# MP_Relay_Control.net
KiCad netlist of a schematic drawn in Altium Designer
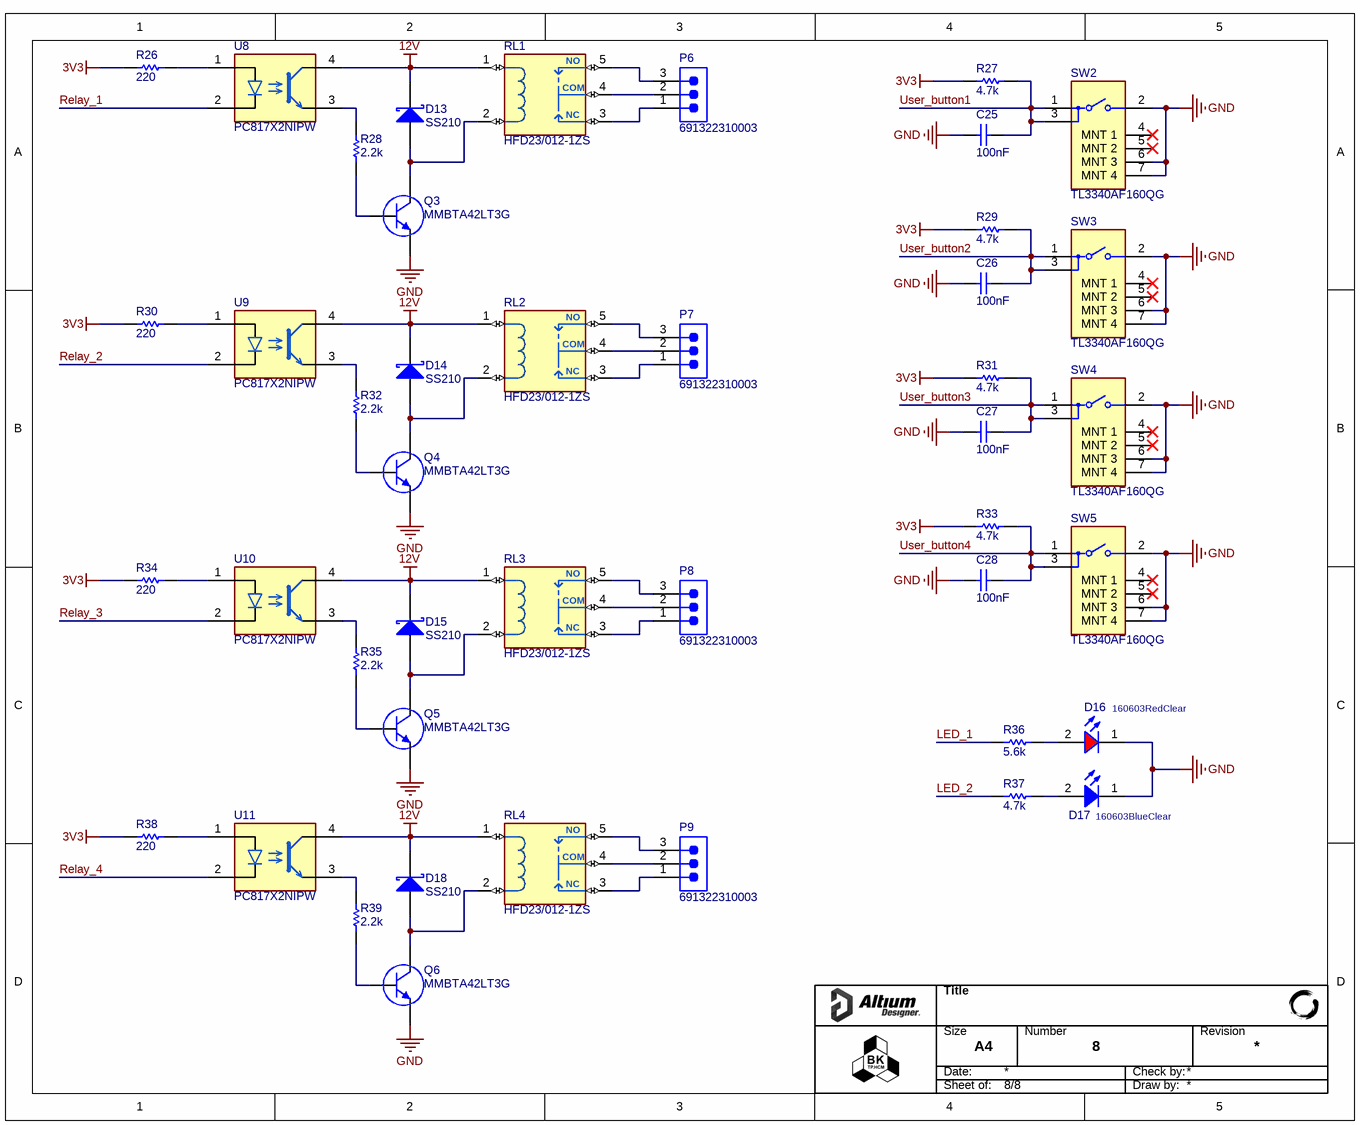
[diagram p0: [MP] Relay Control.SchDoc]

(export (version "E")
  (design (tool "Eeschema 10.0.6"))
  (components
    (comp (ref "C25")
      (value "100nF")
      (footprint "CAP_0603")
      (description "CAP, size 0603, 100 nF, 50 VDC, 10%")
      (fields
        (field (name "TOLERANCE") "10%")
        (field (name "LCSC PART #") "C14663")
        (field (name "SOURCE") "Capacitor_0603_10_percent.SchLib")
      )
      (libsource (lib "University of Technology") (part "010603475106.3"))
    )
    (comp (ref "C26")
      (value "100nF")
      (footprint "CAP_0603")
      (description "CAP, size 0603, 100 nF, 50 VDC, 10%")
      (fields
        (field (name "TOLERANCE") "10%")
        (field (name "LCSC PART #") "C14663")
        (field (name "SOURCE") "Capacitor_0603_10_percent.SchLib")
      )
      (libsource (lib "University of Technology") (part "010603475106.3"))
    )
    (comp (ref "C27")
      (value "100nF")
      (footprint "CAP_0603")
      (description "CAP, size 0603, 100 nF, 50 VDC, 10%")
      (fields
        (field (name "TOLERANCE") "10%")
        (field (name "LCSC PART #") "C14663")
        (field (name "SOURCE") "Capacitor_0603_10_percent.SchLib")
      )
      (libsource (lib "University of Technology") (part "010603475106.3"))
    )
    (comp (ref "C28")
      (value "100nF")
      (footprint "CAP_0603")
      (description "CAP, size 0603, 100 nF, 50 VDC, 10%")
      (fields
        (field (name "TOLERANCE") "10%")
        (field (name "LCSC PART #") "C14663")
        (field (name "SOURCE") "Capacitor_0603_10_percent.SchLib")
      )
      (libsource (lib "University of Technology") (part "010603475106.3"))
    )
    (comp (ref "D13")
      (value "SS210")
      (footprint "SS210-Footprint-SMA")
      (description "Rectifier Diode, Schottky, 1 Phase, 1 Element, 1.5A, 100V V(RRM), Silicon, DO-214AA")
      (libsource (lib "University of Technology") (part "SS210"))
    )
    (comp (ref "D14")
      (value "SS210")
      (footprint "SS210-Footprint-SMA")
      (description "Rectifier Diode, Schottky, 1 Phase, 1 Element, 1.5A, 100V V(RRM), Silicon, DO-214AA")
      (libsource (lib "University of Technology") (part "SS210"))
    )
    (comp (ref "D15")
      (value "SS210")
      (footprint "SS210-Footprint-SMA")
      (description "Rectifier Diode, Schottky, 1 Phase, 1 Element, 1.5A, 100V V(RRM), Silicon, DO-214AA")
      (libsource (lib "University of Technology") (part "SS210"))
    )
    (comp (ref "D16")
      (value "160603RedClear")
      (footprint "WL-SMCW_0603_H=0.7mm")
      (description "WL-SMCW SMT Mono-color Chip LED Waterclear, size 0603, Red, 2V, 140deg")
      (libsource (lib "University of Technology") (part "160603RedClear"))
    )
    (comp (ref "D17")
      (value "160603BlueClear")
      (footprint "WL-SMCW_0603_H=0.7mm")
      (description "WL-SMCW SMT Mono-color Chip LED Waterclear, size 0603, Blue, 3.2V, 140deg")
      (libsource (lib "University of Technology") (part "160603BlueClear"))
    )
    (comp (ref "D18")
      (value "SS210")
      (footprint "SS210-Footprint-SMA")
      (description "Rectifier Diode, Schottky, 1 Phase, 1 Element, 1.5A, 100V V(RRM), Silicon, DO-214AA")
      (libsource (lib "University of Technology") (part "SS210"))
    )
    (comp (ref "P6")
      (value "691322310003")
      (footprint "691322310003")
      (description "WR-TBL Series 322 Horizontal PCB Header, THT, pitch 3.81mm, 3p")
      (fields
        (field (name "MANUFACTURER") "Wurth Elektronik")
        (field (name "SOURCE") "Terminal_Blocks_Pluggable_3.81mm.SchLib")
      )
      (libsource (lib "University of Technology") (part "691322310003"))
    )
    (comp (ref "P7")
      (value "691322310003")
      (footprint "691322310003")
      (description "WR-TBL Series 322 Horizontal PCB Header, THT, pitch 3.81mm, 3p")
      (fields
        (field (name "MANUFACTURER") "Wurth Elektronik")
        (field (name "SOURCE") "Terminal_Blocks_Pluggable_3.81mm.SchLib")
      )
      (libsource (lib "University of Technology") (part "691322310003"))
    )
    (comp (ref "P8")
      (value "691322310003")
      (footprint "691322310003")
      (description "WR-TBL Series 322 Horizontal PCB Header, THT, pitch 3.81mm, 3p")
      (fields
        (field (name "MANUFACTURER") "Wurth Elektronik")
        (field (name "SOURCE") "Terminal_Blocks_Pluggable_3.81mm.SchLib")
      )
      (libsource (lib "University of Technology") (part "691322310003"))
    )
    (comp (ref "P9")
      (value "691322310003")
      (footprint "691322310003")
      (description "WR-TBL Series 322 Horizontal PCB Header, THT, pitch 3.81mm, 3p")
      (fields
        (field (name "MANUFACTURER") "Wurth Elektronik")
        (field (name "SOURCE") "Terminal_Blocks_Pluggable_3.81mm.SchLib")
      )
      (libsource (lib "University of Technology") (part "691322310003"))
    )
    (comp (ref "Q3")
      (value "MMBTA42LT3G")
      (footprint "ONSC-SOT-23-3-318-08_V")
      (description "Small Signal Bipolar Transistor, 0.5A I(C), 300V V(BR)CEO, 1-Element, NPN, Silicon, TO-236AB")
      (libsource (lib "University of Technology") (part "TRANS-NPN-3"))
    )
    (comp (ref "Q4")
      (value "MMBTA42LT3G")
      (footprint "ONSC-SOT-23-3-318-08_V")
      (description "Small Signal Bipolar Transistor, 0.5A I(C), 300V V(BR)CEO, 1-Element, NPN, Silicon, TO-236AB")
      (libsource (lib "University of Technology") (part "TRANS-NPN-3"))
    )
    (comp (ref "Q5")
      (value "MMBTA42LT3G")
      (footprint "ONSC-SOT-23-3-318-08_V")
      (description "Small Signal Bipolar Transistor, 0.5A I(C), 300V V(BR)CEO, 1-Element, NPN, Silicon, TO-236AB")
      (libsource (lib "University of Technology") (part "TRANS-NPN-3"))
    )
    (comp (ref "Q6")
      (value "MMBTA42LT3G")
      (footprint "ONSC-SOT-23-3-318-08_V")
      (description "Small Signal Bipolar Transistor, 0.5A I(C), 300V V(BR)CEO, 1-Element, NPN, Silicon, TO-236AB")
      (libsource (lib "University of Technology") (part "TRANS-NPN-3"))
    )
    (comp (ref "R26")
      (value "220")
      (footprint "RES_0603")
      (description "RES, size 0603, 220 Ohm, 1/10 W, 1%")
      (fields (field (name "TOLERANCE") "1%") (field (name "MANUFACTURER") "YAGEO"))
      (libsource (lib "University of Technology") (part "00060371541"))
    )
    (comp (ref "R27")
      (value "4.7k")
      (footprint "RES_0603")
      (description "RES, size 0603, 4.7 kOhm, 1/10 W, 1%")
      (fields (field (name "LCSC PART #") "C99782") (field (name "MANUFACTURER") "YAGEO"))
      (libsource (lib "University of Technology") (part "00060371541"))
    )
    (comp (ref "R28")
      (value "2.2k")
      (footprint "RES_0603")
      (description "RES, size 0603, 2.2  KOhm, 1/10 W, 1%")
      (fields (field (name "TOLERANCE") "1%") (field (name "MANUFACTURER PART NUMBER") "OEM"))
      (libsource (lib "University of Technology") (part "00060371541"))
    )
    (comp (ref "R29")
      (value "4.7k")
      (footprint "RES_0603")
      (description "RES, size 0603, 4.7 kOhm, 1/10 W, 1%")
      (fields (field (name "LCSC PART #") "C99782") (field (name "MANUFACTURER") "YAGEO"))
      (libsource (lib "University of Technology") (part "00060371541"))
    )
    (comp (ref "R30")
      (value "220")
      (footprint "RES_0603")
      (description "RES, size 0603, 220 Ohm, 1/10 W, 1%")
      (fields (field (name "TOLERANCE") "1%") (field (name "MANUFACTURER") "YAGEO"))
      (libsource (lib "University of Technology") (part "00060371541"))
    )
    (comp (ref "R31")
      (value "4.7k")
      (footprint "RES_0603")
      (description "RES, size 0603, 4.7 kOhm, 1/10 W, 1%")
      (fields (field (name "LCSC PART #") "C99782") (field (name "MANUFACTURER") "YAGEO"))
      (libsource (lib "University of Technology") (part "00060371541"))
    )
    (comp (ref "R32")
      (value "2.2k")
      (footprint "RES_0603")
      (description "RES, size 0603, 2.2  KOhm, 1/10 W, 1%")
      (fields (field (name "TOLERANCE") "1%") (field (name "MANUFACTURER PART NUMBER") "OEM"))
      (libsource (lib "University of Technology") (part "00060371541"))
    )
    (comp (ref "R33")
      (value "4.7k")
      (footprint "RES_0603")
      (description "RES, size 0603, 4.7 kOhm, 1/10 W, 1%")
      (fields (field (name "LCSC PART #") "C99782") (field (name "MANUFACTURER") "YAGEO"))
      (libsource (lib "University of Technology") (part "00060371541"))
    )
    (comp (ref "R34")
      (value "220")
      (footprint "RES_0603")
      (description "RES, size 0603, 220 Ohm, 1/10 W, 1%")
      (fields (field (name "TOLERANCE") "1%") (field (name "MANUFACTURER") "YAGEO"))
      (libsource (lib "University of Technology") (part "00060371541"))
    )
    (comp (ref "R35")
      (value "2.2k")
      (footprint "RES_0603")
      (description "RES, size 0603, 2.2  KOhm, 1/10 W, 1%")
      (fields (field (name "TOLERANCE") "1%") (field (name "MANUFACTURER PART NUMBER") "OEM"))
      (libsource (lib "University of Technology") (part "00060371541"))
    )
    (comp (ref "R36")
      (value "5.6k")
      (footprint "RES_0603")
      (description "RES, size 0603, 5.6 KOhm, 1/10 W, 1%")
      (fields (field (name "MANUFACTURER PART NUMBER") "OEM") (field (name "TOLERANCE") "1%"))
      (libsource (lib "University of Technology") (part "00060371541"))
    )
    (comp (ref "R37")
      (value "4.7k")
      (footprint "RES_0603")
      (description "RES, size 0603, 4.7 kOhm, 1/10 W, 1%")
      (fields (field (name "LCSC PART #") "C99782") (field (name "MANUFACTURER") "YAGEO"))
      (libsource (lib "University of Technology") (part "00060371541"))
    )
    (comp (ref "R38")
      (value "220")
      (footprint "RES_0603")
      (description "RES, size 0603, 220 Ohm, 1/10 W, 1%")
      (fields (field (name "TOLERANCE") "1%") (field (name "MANUFACTURER") "YAGEO"))
      (libsource (lib "University of Technology") (part "00060371541"))
    )
    (comp (ref "R39")
      (value "2.2k")
      (footprint "RES_0603")
      (description "RES, size 0603, 2.2  KOhm, 1/10 W, 1%")
      (fields (field (name "TOLERANCE") "1%") (field (name "MANUFACTURER PART NUMBER") "OEM"))
      (libsource (lib "University of Technology") (part "00060371541"))
    )
    (comp (ref "RL1")
      (value "HFD23/012-1ZS")
      (footprint "HFD23_012-1ZS-Footprint-1")
      (libsource (lib "University of Technology") (part "HFD23_012-1ZS"))
    )
    (comp (ref "RL2")
      (value "HFD23/012-1ZS")
      (footprint "HFD23_012-1ZS-Footprint-1")
      (libsource (lib "University of Technology") (part "HFD23_012-1ZS"))
    )
    (comp (ref "RL3")
      (value "HFD23/012-1ZS")
      (footprint "HFD23_012-1ZS-Footprint-1")
      (libsource (lib "University of Technology") (part "HFD23_012-1ZS"))
    )
    (comp (ref "RL4")
      (value "HFD23/012-1ZS")
      (footprint "HFD23_012-1ZS-Footprint-1")
      (libsource (lib "University of Technology") (part "HFD23_012-1ZS"))
    )
    (comp (ref "SW2")
      (value "TL3340AF160QG")
      (footprint "FP-TL3340AF160QG-MFG")
      (libsource (lib "University of Technology") (part "84f95d6c02d60e4bec2cc0c17c5926e"))
    )
    (comp (ref "SW3")
      (value "TL3340AF160QG")
      (footprint "FP-TL3340AF160QG-MFG")
      (libsource (lib "University of Technology") (part "84f95d6c02d60e4bec2cc0c17c5926e"))
    )
    (comp (ref "SW4")
      (value "TL3340AF160QG")
      (footprint "FP-TL3340AF160QG-MFG")
      (libsource (lib "University of Technology") (part "84f95d6c02d60e4bec2cc0c17c5926e"))
    )
    (comp (ref "SW5")
      (value "TL3340AF160QG")
      (footprint "FP-TL3340AF160QG-MFG")
      (libsource (lib "University of Technology") (part "84f95d6c02d60e4bec2cc0c17c5926e"))
    )
    (comp (ref "U8")
      (value "PC817X2NIPW")
      (footprint "PC817X2NIPW-Footprint")
      (description "PC817 series, SMD, I_F (max) = 500mA, V_F (max) = 1.4V.")
      (libsource (lib "University of Technology") (part "New symbol 1"))
    )
    (comp (ref "U9")
      (value "PC817X2NIPW")
      (footprint "PC817X2NIPW-Footprint")
      (description "PC817 series, SMD, I_F (max) = 500mA, V_F (max) = 1.4V.")
      (libsource (lib "University of Technology") (part "New symbol 1"))
    )
    (comp (ref "U10")
      (value "PC817X2NIPW")
      (footprint "PC817X2NIPW-Footprint")
      (description "PC817 series, SMD, I_F (max) = 500mA, V_F (max) = 1.4V.")
      (libsource (lib "University of Technology") (part "New symbol 1"))
    )
    (comp (ref "U11")
      (value "PC817X2NIPW")
      (footprint "PC817X2NIPW-Footprint")
      (description "PC817 series, SMD, I_F (max) = 500mA, V_F (max) = 1.4V.")
      (libsource (lib "University of Technology") (part "New symbol 1"))
    )
  )
  (nets
    (net (code "1") (name "/LED_1") (class "Default")
      (node (ref "R36") (pin "1") (pinfunction "1_1") (pintype "passive"))
    )
    (net (code "2") (name "/LED_2") (class "Default")
      (node (ref "R37") (pin "1") (pinfunction "1_1") (pintype "passive"))
    )
    (net (code "3") (name "/Relay_1") (class "Default")
      (node (ref "U8") (pin "2") (pinfunction "2_2") (pintype "passive"))
    )
    (net (code "4") (name "/Relay_2") (class "Default")
      (node (ref "U9") (pin "2") (pinfunction "2_2") (pintype "passive"))
    )
    (net (code "5") (name "/Relay_3") (class "Default")
      (node (ref "U10") (pin "2") (pinfunction "2_2") (pintype "passive"))
    )
    (net (code "6") (name "/Relay_4") (class "Default")
      (node (ref "U11") (pin "2") (pinfunction "2_2") (pintype "passive"))
    )
    (net (code "7") (name "/User_button1") (class "Default")
      (node (ref "C25") (pin "2") (pinfunction "2_2") (pintype "passive"))
      (node (ref "R27") (pin "2") (pinfunction "2_2") (pintype "passive"))
      (node (ref "SW2") (pin "1") (pinfunction "1_1") (pintype "passive"))
      (node (ref "SW2") (pin "3") (pinfunction "3_3") (pintype "passive"))
    )
    (net (code "8") (name "/User_button2") (class "Default")
      (node (ref "C26") (pin "2") (pinfunction "2_2") (pintype "passive"))
      (node (ref "R29") (pin "2") (pinfunction "2_2") (pintype "passive"))
      (node (ref "SW3") (pin "1") (pinfunction "1_1") (pintype "passive"))
      (node (ref "SW3") (pin "3") (pinfunction "3_3") (pintype "passive"))
    )
    (net (code "9") (name "/User_button3") (class "Default")
      (node (ref "C27") (pin "2") (pinfunction "2_2") (pintype "passive"))
      (node (ref "R31") (pin "2") (pinfunction "2_2") (pintype "passive"))
      (node (ref "SW4") (pin "1") (pinfunction "1_1") (pintype "passive"))
      (node (ref "SW4") (pin "3") (pinfunction "3_3") (pintype "passive"))
    )
    (net (code "10") (name "/User_button4") (class "Default")
      (node (ref "C28") (pin "2") (pinfunction "2_2") (pintype "passive"))
      (node (ref "R33") (pin "2") (pinfunction "2_2") (pintype "passive"))
      (node (ref "SW5") (pin "1") (pinfunction "1_1") (pintype "passive"))
      (node (ref "SW5") (pin "3") (pinfunction "3_3") (pintype "passive"))
    )
    (net (code "11") (name "3V3") (class "Default")
      (node (ref "R26") (pin "1") (pinfunction "1_1") (pintype "passive"))
      (node (ref "R27") (pin "1") (pinfunction "1_1") (pintype "passive"))
      (node (ref "R29") (pin "1") (pinfunction "1_1") (pintype "passive"))
      (node (ref "R30") (pin "1") (pinfunction "1_1") (pintype "passive"))
      (node (ref "R31") (pin "1") (pinfunction "1_1") (pintype "passive"))
      (node (ref "R33") (pin "1") (pinfunction "1_1") (pintype "passive"))
      (node (ref "R34") (pin "1") (pinfunction "1_1") (pintype "passive"))
      (node (ref "R38") (pin "1") (pinfunction "1_1") (pintype "passive"))
    )
    (net (code "12") (name "12V") (class "Default")
      (node (ref "D13") (pin "2") (pinfunction "K_2") (pintype "passive"))
      (node (ref "D14") (pin "2") (pinfunction "K_2") (pintype "passive"))
      (node (ref "D15") (pin "2") (pinfunction "K_2") (pintype "passive"))
      (node (ref "D18") (pin "2") (pinfunction "K_2") (pintype "passive"))
      (node (ref "RL1") (pin "1") (pinfunction "C1_1") (pintype "bidirectional"))
      (node (ref "RL2") (pin "1") (pinfunction "C1_1") (pintype "bidirectional"))
      (node (ref "RL3") (pin "1") (pinfunction "C1_1") (pintype "bidirectional"))
      (node (ref "RL4") (pin "1") (pinfunction "C1_1") (pintype "bidirectional"))
      (node (ref "U10") (pin "4") (pinfunction "4_4") (pintype "passive"))
      (node (ref "U11") (pin "4") (pinfunction "4_4") (pintype "passive"))
      (node (ref "U8") (pin "4") (pinfunction "4_4") (pintype "passive"))
      (node (ref "U9") (pin "4") (pinfunction "4_4") (pintype "passive"))
    )
    (net (code "13") (name "GND") (class "Default")
      (node (ref "C25") (pin "1") (pinfunction "1_1") (pintype "passive"))
      (node (ref "C26") (pin "1") (pinfunction "1_1") (pintype "passive"))
      (node (ref "C27") (pin "1") (pinfunction "1_1") (pintype "passive"))
      (node (ref "C28") (pin "1") (pinfunction "1_1") (pintype "passive"))
      (node (ref "D16") (pin "1") (pinfunction "K_1") (pintype "passive"))
      (node (ref "D17") (pin "1") (pinfunction "K_1") (pintype "passive"))
      (node (ref "Q3") (pin "2") (pinfunction "E_2") (pintype "passive"))
      (node (ref "Q4") (pin "2") (pinfunction "E_2") (pintype "passive"))
      (node (ref "Q5") (pin "2") (pinfunction "E_2") (pintype "passive"))
      (node (ref "Q6") (pin "2") (pinfunction "E_2") (pintype "passive"))
      (node (ref "SW2") (pin "2") (pinfunction "2_2") (pintype "passive"))
      (node (ref "SW2") (pin "6") (pinfunction "MNT_3_6") (pintype "passive"))
      (node (ref "SW2") (pin "7") (pinfunction "MNT_4_7") (pintype "passive"))
      (node (ref "SW3") (pin "2") (pinfunction "2_2") (pintype "passive"))
      (node (ref "SW3") (pin "6") (pinfunction "MNT_3_6") (pintype "passive"))
      (node (ref "SW3") (pin "7") (pinfunction "MNT_4_7") (pintype "passive"))
      (node (ref "SW4") (pin "2") (pinfunction "2_2") (pintype "passive"))
      (node (ref "SW4") (pin "6") (pinfunction "MNT_3_6") (pintype "passive"))
      (node (ref "SW4") (pin "7") (pinfunction "MNT_4_7") (pintype "passive"))
      (node (ref "SW5") (pin "2") (pinfunction "2_2") (pintype "passive"))
      (node (ref "SW5") (pin "6") (pinfunction "MNT_3_6") (pintype "passive"))
      (node (ref "SW5") (pin "7") (pinfunction "MNT_4_7") (pintype "passive"))
    )
    (net (code "14") (name "Net-(D13-A)") (class "Default")
      (node (ref "D13") (pin "1") (pinfunction "A_1") (pintype "passive"))
      (node (ref "Q3") (pin "3") (pinfunction "C_3") (pintype "passive"))
      (node (ref "RL1") (pin "2") (pinfunction "C2_2") (pintype "bidirectional"))
    )
    (net (code "15") (name "Net-(D14-A)") (class "Default")
      (node (ref "D14") (pin "1") (pinfunction "A_1") (pintype "passive"))
      (node (ref "Q4") (pin "3") (pinfunction "C_3") (pintype "passive"))
      (node (ref "RL2") (pin "2") (pinfunction "C2_2") (pintype "bidirectional"))
    )
    (net (code "16") (name "Net-(D15-A)") (class "Default")
      (node (ref "D15") (pin "1") (pinfunction "A_1") (pintype "passive"))
      (node (ref "Q5") (pin "3") (pinfunction "C_3") (pintype "passive"))
      (node (ref "RL3") (pin "2") (pinfunction "C2_2") (pintype "bidirectional"))
    )
    (net (code "17") (name "Net-(D16-A)") (class "Default")
      (node (ref "D16") (pin "2") (pinfunction "A_2") (pintype "passive"))
      (node (ref "R36") (pin "2") (pinfunction "2_2") (pintype "passive"))
    )
    (net (code "18") (name "Net-(D17-A)") (class "Default")
      (node (ref "D17") (pin "2") (pinfunction "A_2") (pintype "passive"))
      (node (ref "R37") (pin "2") (pinfunction "2_2") (pintype "passive"))
    )
    (net (code "19") (name "Net-(D18-A)") (class "Default")
      (node (ref "D18") (pin "1") (pinfunction "A_1") (pintype "passive"))
      (node (ref "Q6") (pin "3") (pinfunction "C_3") (pintype "passive"))
      (node (ref "RL4") (pin "2") (pinfunction "C2_2") (pintype "bidirectional"))
    )
    (net (code "20") (name "Net-(P6-Pad2)") (class "Default")
      (node (ref "P6") (pin "2") (pinfunction "2_2") (pintype "passive"))
      (node (ref "RL1") (pin "4") (pinfunction "C_4") (pintype "bidirectional"))
    )
    (net (code "21") (name "Net-(P6-Pad3)") (class "Default")
      (node (ref "P6") (pin "3") (pinfunction "3_3") (pintype "passive"))
      (node (ref "RL1") (pin "5") (pinfunction "C_5") (pintype "bidirectional"))
    )
    (net (code "22") (name "Net-(P7-Pad2)") (class "Default")
      (node (ref "P7") (pin "2") (pinfunction "2_2") (pintype "passive"))
      (node (ref "RL2") (pin "4") (pinfunction "C_4") (pintype "bidirectional"))
    )
    (net (code "23") (name "Net-(P7-Pad3)") (class "Default")
      (node (ref "P7") (pin "3") (pinfunction "3_3") (pintype "passive"))
      (node (ref "RL2") (pin "5") (pinfunction "C_5") (pintype "bidirectional"))
    )
    (net (code "24") (name "Net-(P8-Pad2)") (class "Default")
      (node (ref "P8") (pin "2") (pinfunction "2_2") (pintype "passive"))
      (node (ref "RL3") (pin "4") (pinfunction "C_4") (pintype "bidirectional"))
    )
    (net (code "25") (name "Net-(P8-Pad3)") (class "Default")
      (node (ref "P8") (pin "3") (pinfunction "3_3") (pintype "passive"))
      (node (ref "RL3") (pin "5") (pinfunction "C_5") (pintype "bidirectional"))
    )
    (net (code "26") (name "Net-(P9-Pad2)") (class "Default")
      (node (ref "P9") (pin "2") (pinfunction "2_2") (pintype "passive"))
      (node (ref "RL4") (pin "4") (pinfunction "C_4") (pintype "bidirectional"))
    )
    (net (code "27") (name "Net-(P9-Pad3)") (class "Default")
      (node (ref "P9") (pin "3") (pinfunction "3_3") (pintype "passive"))
      (node (ref "RL4") (pin "5") (pinfunction "C_5") (pintype "bidirectional"))
    )
    (net (code "28") (name "Net-(Q3-B)") (class "Default")
      (node (ref "Q3") (pin "1") (pinfunction "B_1") (pintype "passive"))
      (node (ref "R28") (pin "1") (pinfunction "1_1") (pintype "passive"))
    )
    (net (code "29") (name "Net-(Q4-B)") (class "Default")
      (node (ref "Q4") (pin "1") (pinfunction "B_1") (pintype "passive"))
      (node (ref "R32") (pin "1") (pinfunction "1_1") (pintype "passive"))
    )
    (net (code "30") (name "Net-(Q5-B)") (class "Default")
      (node (ref "Q5") (pin "1") (pinfunction "B_1") (pintype "passive"))
      (node (ref "R35") (pin "1") (pinfunction "1_1") (pintype "passive"))
    )
    (net (code "31") (name "Net-(Q6-B)") (class "Default")
      (node (ref "Q6") (pin "1") (pinfunction "B_1") (pintype "passive"))
      (node (ref "R39") (pin "1") (pinfunction "1_1") (pintype "passive"))
    )
    (net (code "32") (name "Net-(R26-Pad2)") (class "Default")
      (node (ref "R26") (pin "2") (pinfunction "2_2") (pintype "passive"))
      (node (ref "U8") (pin "1") (pinfunction "1_1") (pintype "passive"))
    )
    (net (code "33") (name "Net-(R28-Pad2)") (class "Default")
      (node (ref "R28") (pin "2") (pinfunction "2_2") (pintype "passive"))
      (node (ref "U8") (pin "3") (pinfunction "3_3") (pintype "passive"))
    )
    (net (code "34") (name "Net-(R30-Pad2)") (class "Default")
      (node (ref "R30") (pin "2") (pinfunction "2_2") (pintype "passive"))
      (node (ref "U9") (pin "1") (pinfunction "1_1") (pintype "passive"))
    )
    (net (code "35") (name "Net-(R32-Pad2)") (class "Default")
      (node (ref "R32") (pin "2") (pinfunction "2_2") (pintype "passive"))
      (node (ref "U9") (pin "3") (pinfunction "3_3") (pintype "passive"))
    )
    (net (code "36") (name "Net-(R34-Pad2)") (class "Default")
      (node (ref "R34") (pin "2") (pinfunction "2_2") (pintype "passive"))
      (node (ref "U10") (pin "1") (pinfunction "1_1") (pintype "passive"))
    )
    (net (code "37") (name "Net-(R35-Pad2)") (class "Default")
      (node (ref "R35") (pin "2") (pinfunction "2_2") (pintype "passive"))
      (node (ref "U10") (pin "3") (pinfunction "3_3") (pintype "passive"))
    )
    (net (code "38") (name "Net-(R38-Pad2)") (class "Default")
      (node (ref "R38") (pin "2") (pinfunction "2_2") (pintype "passive"))
      (node (ref "U11") (pin "1") (pinfunction "1_1") (pintype "passive"))
    )
    (net (code "39") (name "Net-(R39-Pad2)") (class "Default")
      (node (ref "R39") (pin "2") (pinfunction "2_2") (pintype "passive"))
      (node (ref "U11") (pin "3") (pinfunction "3_3") (pintype "passive"))
    )
    (net (code "40") (name "Net-(RL1-NO)") (class "Default")
      (node (ref "P6") (pin "1") (pinfunction "1_1") (pintype "passive"))
      (node (ref "RL1") (pin "3") (pinfunction "NO_3") (pintype "bidirectional"))
    )
    (net (code "41") (name "Net-(RL2-NO)") (class "Default")
      (node (ref "P7") (pin "1") (pinfunction "1_1") (pintype "passive"))
      (node (ref "RL2") (pin "3") (pinfunction "NO_3") (pintype "bidirectional"))
    )
    (net (code "42") (name "Net-(RL3-NO)") (class "Default")
      (node (ref "P8") (pin "1") (pinfunction "1_1") (pintype "passive"))
      (node (ref "RL3") (pin "3") (pinfunction "NO_3") (pintype "bidirectional"))
    )
    (net (code "43") (name "Net-(RL4-NO)") (class "Default")
      (node (ref "P9") (pin "1") (pinfunction "1_1") (pintype "passive"))
      (node (ref "RL4") (pin "3") (pinfunction "NO_3") (pintype "bidirectional"))
    )
    (net (code "44") (name "unconnected-(SW2-MNT_1-Pad4)") (class "Default")
      (node (ref "SW2") (pin "4") (pinfunction "MNT_1_4") (pintype "passive+no_connect"))
    )
    (net (code "45") (name "unconnected-(SW2-MNT_2-Pad5)") (class "Default")
      (node (ref "SW2") (pin "5") (pinfunction "MNT_2_5") (pintype "passive+no_connect"))
    )
    (net (code "46") (name "unconnected-(SW3-MNT_1-Pad4)") (class "Default")
      (node (ref "SW3") (pin "4") (pinfunction "MNT_1_4") (pintype "passive+no_connect"))
    )
    (net (code "47") (name "unconnected-(SW3-MNT_2-Pad5)") (class "Default")
      (node (ref "SW3") (pin "5") (pinfunction "MNT_2_5") (pintype "passive+no_connect"))
    )
    (net (code "48") (name "unconnected-(SW4-MNT_1-Pad4)") (class "Default")
      (node (ref "SW4") (pin "4") (pinfunction "MNT_1_4") (pintype "passive+no_connect"))
    )
    (net (code "49") (name "unconnected-(SW4-MNT_2-Pad5)") (class "Default")
      (node (ref "SW4") (pin "5") (pinfunction "MNT_2_5") (pintype "passive+no_connect"))
    )
    (net (code "50") (name "unconnected-(SW5-MNT_1-Pad4)") (class "Default")
      (node (ref "SW5") (pin "4") (pinfunction "MNT_1_4") (pintype "passive+no_connect"))
    )
    (net (code "51") (name "unconnected-(SW5-MNT_2-Pad5)") (class "Default")
      (node (ref "SW5") (pin "5") (pinfunction "MNT_2_5") (pintype "passive+no_connect"))
    )
  )
)
